# Wind_enc_INSP.net
KiCad netlist of a schematic drawn in EAGLE
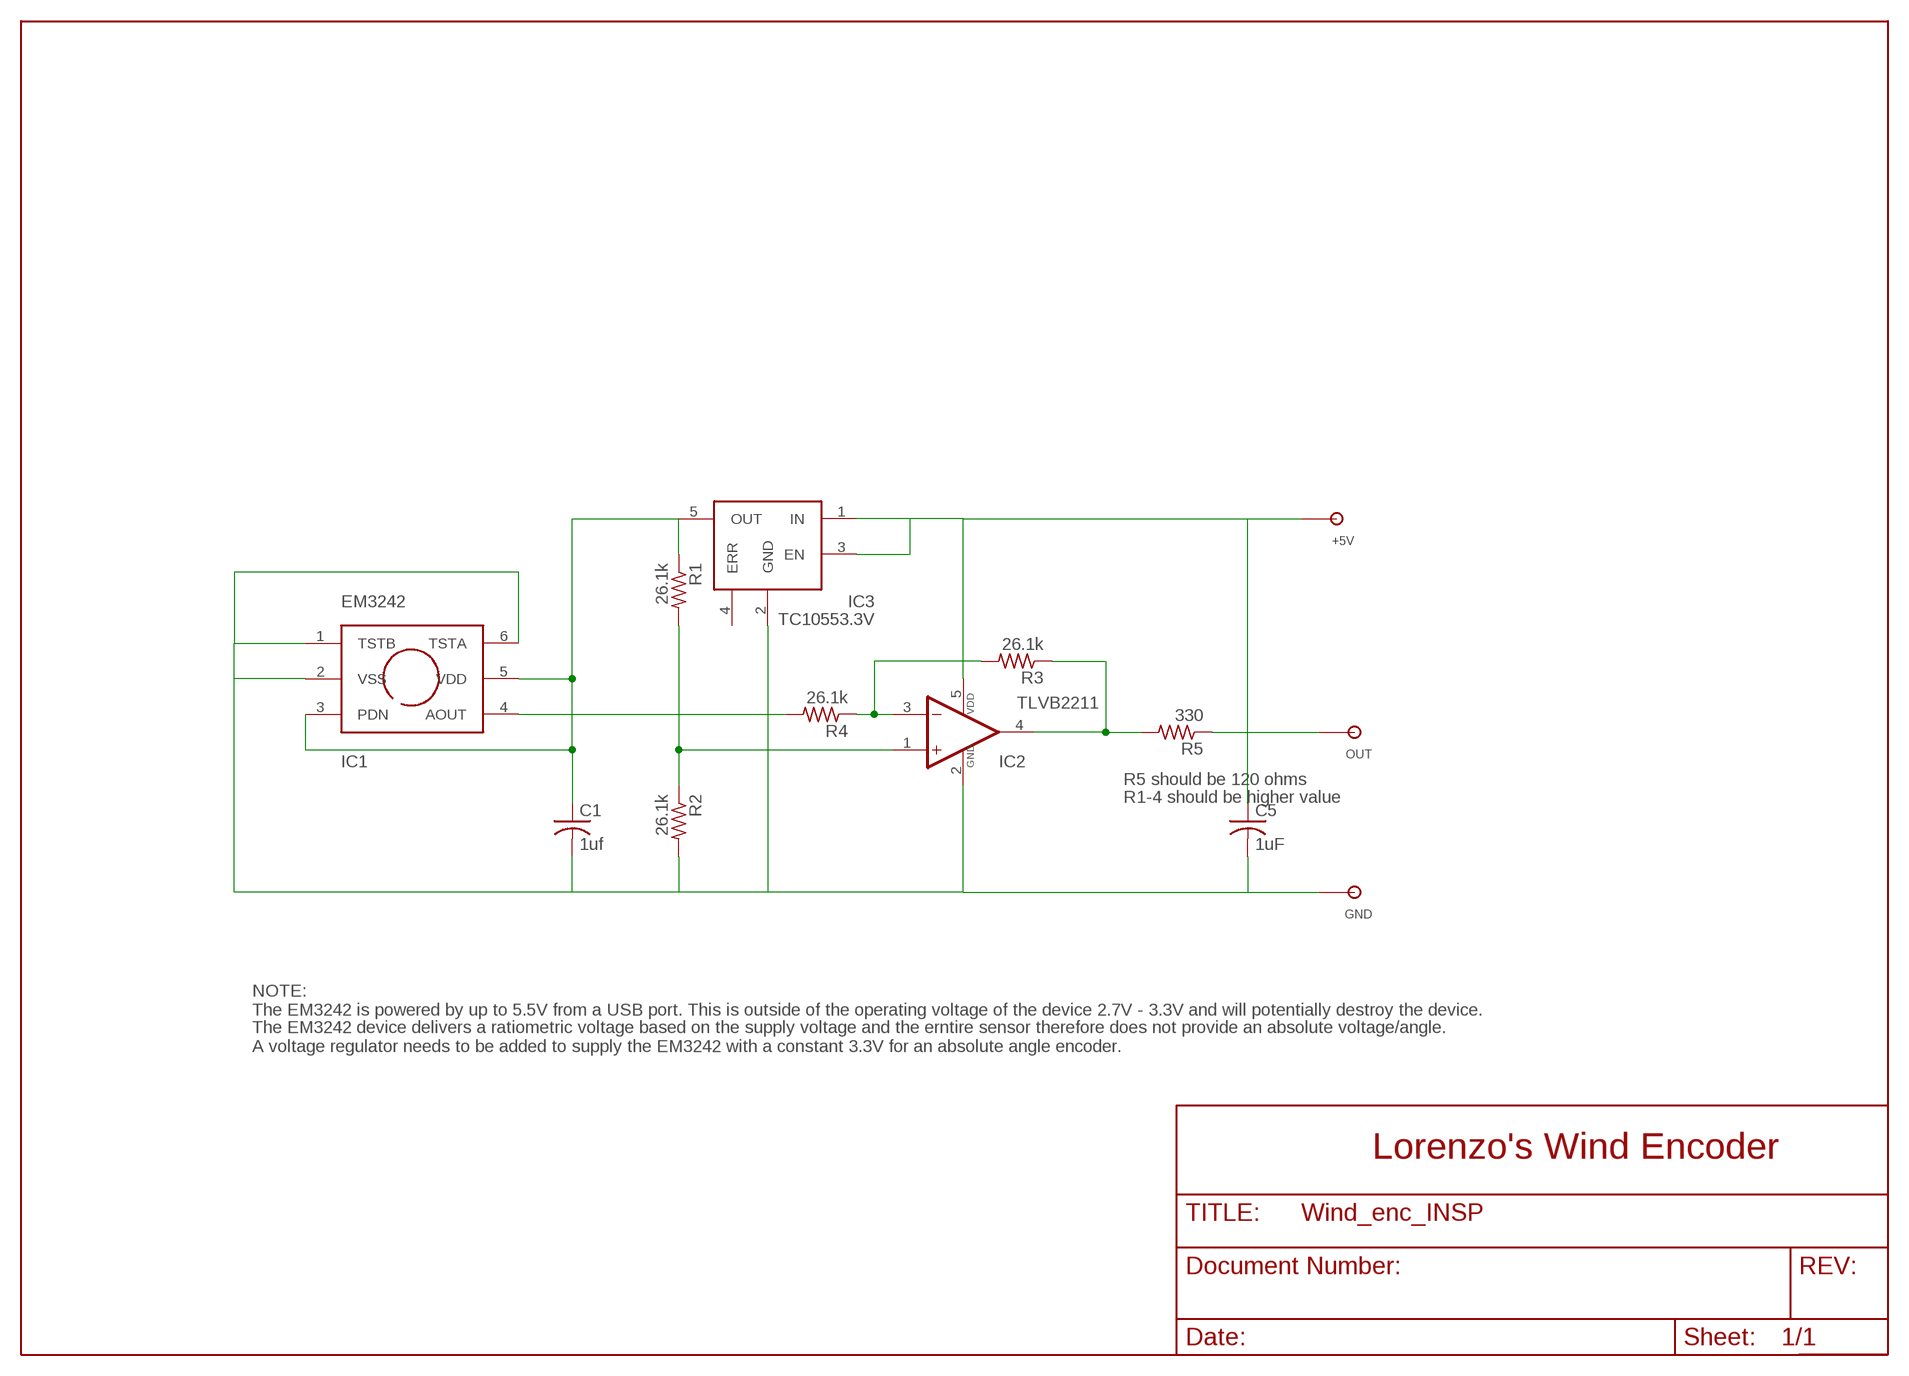
[diagram p0: schematic, sheet 1]

(export (version "E")
  (design (tool "Eeschema 10.0.6"))
  (components
    (comp (ref "+5V")
      (value "TPSOL")
      (footprint "eagle-import:TP_SOL")
      (libsource (lib "eagle-import") (part "TPSOL"))
    )
    (comp (ref "C1")
      (value "1uf")
      (footprint "eagle-import:C0805K")
      (libsource (lib "eagle-import") (part "C-USC0805K"))
    )
    (comp (ref "C5")
      (value "1uF")
      (footprint "eagle-import:C0805K")
      (libsource (lib "eagle-import") (part "C-USC0805K"))
    )
    (comp (ref "GND")
      (value "TPSOL")
      (footprint "eagle-import:TP_SOL")
      (libsource (lib "eagle-import") (part "TPSOL"))
    )
    (comp (ref "IC1")
      (value "EM3242")
      (footprint "eagle-import:EM3242_SPECIAL")
      (libsource (lib "eagle-import") (part "EM3242"))
    )
    (comp (ref "IC2")
      (value "TLVB2211")
      (footprint "eagle-import:SOT23-5")
      (libsource (lib "eagle-import") (part "TLVB2211"))
    )
    (comp (ref "IC3")
      (value "TC10553.3V")
      (footprint "eagle-import:SOT23-5")
      (libsource (lib "eagle-import") (part "TC10553.3V"))
    )
    (comp (ref "OUT")
      (value "TPSOL")
      (footprint "eagle-import:TP_SOL")
      (libsource (lib "eagle-import") (part "TPSOL"))
    )
    (comp (ref "R1")
      (value "26.1k")
      (footprint "eagle-import:R0603")
      (libsource (lib "eagle-import") (part "R-US_R0603"))
    )
    (comp (ref "R2")
      (value "26.1k")
      (footprint "eagle-import:R0603")
      (libsource (lib "eagle-import") (part "R-US_R0603"))
    )
    (comp (ref "R3")
      (value "26.1k")
      (footprint "eagle-import:R0603")
      (libsource (lib "eagle-import") (part "R-US_R0603"))
    )
    (comp (ref "R4")
      (value "26.1k")
      (footprint "eagle-import:R0603")
      (libsource (lib "eagle-import") (part "R-US_R0603"))
    )
    (comp (ref "R5")
      (value "330")
      (footprint "eagle-import:R0603")
      (libsource (lib "eagle-import") (part "R-US_R0603"))
    )
  )
  (nets
    (net (code "1") (name "Net-(IC1-AOUT)") (class "Default")
      (node (ref "IC1") (pin "4") (pinfunction "AOUT_4") (pintype "bidirectional"))
      (node (ref "R4") (pin "2") (pinfunction "2_2") (pintype "passive"))
    )
    (net (code "2") (name "Net-(IC1-PDN)") (class "Default")
      (node (ref "C1") (pin "1") (pinfunction "1_1") (pintype "passive"))
      (node (ref "IC1") (pin "3") (pinfunction "PDN_3") (pintype "bidirectional"))
      (node (ref "IC1") (pin "5") (pinfunction "VDD_5") (pintype "bidirectional"))
      (node (ref "IC3") (pin "5") (pinfunction "OUT_5") (pintype "power_in"))
      (node (ref "R1") (pin "1") (pinfunction "1_1") (pintype "passive"))
    )
    (net (code "3") (name "Net-(IC1-TSTA)") (class "Default")
      (node (ref "C1") (pin "2") (pinfunction "2_2") (pintype "passive"))
      (node (ref "C5") (pin "2") (pinfunction "2_2") (pintype "passive"))
      (node (ref "GND") (pin "P$1") (pinfunction "P$1_P$1") (pintype "bidirectional"))
      (node (ref "IC1") (pin "1") (pinfunction "TSTB_1") (pintype "bidirectional"))
      (node (ref "IC1") (pin "2") (pinfunction "VSS_2") (pintype "bidirectional"))
      (node (ref "IC1") (pin "6") (pinfunction "TSTA_6") (pintype "bidirectional"))
      (node (ref "IC2") (pin "2") (pinfunction "VDD_GND_2") (pintype "power_in"))
      (node (ref "IC3") (pin "2") (pinfunction "GND_2") (pintype "power_in"))
      (node (ref "R2") (pin "2") (pinfunction "2_2") (pintype "passive"))
    )
    (net (code "4") (name "Net-(IC2A-+IN)") (class "Default")
      (node (ref "IC2") (pin "1") (pinfunction "+IN_1") (pintype "input"))
      (node (ref "R1") (pin "2") (pinfunction "2_2") (pintype "passive"))
      (node (ref "R2") (pin "1") (pinfunction "1_1") (pintype "passive"))
    )
    (net (code "5") (name "Net-(IC2A--IN)") (class "Default")
      (node (ref "IC2") (pin "3") (pinfunction "-IN_3") (pintype "input"))
      (node (ref "R3") (pin "2") (pinfunction "2_2") (pintype "passive"))
      (node (ref "R4") (pin "1") (pinfunction "1_1") (pintype "passive"))
    )
    (net (code "6") (name "Net-(IC2A-OUT)") (class "Default")
      (node (ref "IC2") (pin "4") (pinfunction "OUT_4") (pintype "output"))
      (node (ref "R3") (pin "1") (pinfunction "1_1") (pintype "passive"))
      (node (ref "R5") (pin "2") (pinfunction "2_2") (pintype "passive"))
    )
    (net (code "7") (name "Net-(IC2B-VDD)") (class "Default")
      (node (ref "+5V") (pin "P$1") (pinfunction "P$1_P$1") (pintype "bidirectional"))
      (node (ref "C5") (pin "1") (pinfunction "1_1") (pintype "passive"))
      (node (ref "IC2") (pin "5") (pinfunction "VDD_5") (pintype "power_in"))
      (node (ref "IC3") (pin "1") (pinfunction "IN_1") (pintype "power_in"))
      (node (ref "IC3") (pin "3") (pinfunction "EN_3") (pintype "input"))
    )
    (net (code "8") (name "Net-(OUT-PadP$1)") (class "Default")
      (node (ref "OUT") (pin "P$1") (pinfunction "P$1_P$1") (pintype "bidirectional"))
      (node (ref "R5") (pin "1") (pinfunction "1_1") (pintype "passive"))
    )
    (net (code "9") (name "unconnected-(IC3-ERR-Pad4)") (class "Default")
      (node (ref "IC3") (pin "4") (pinfunction "ERR_4") (pintype "output"))
    )
  )
)
